# Pump_Agri.net
KiCad netlist of a schematic drawn in Altium Designer
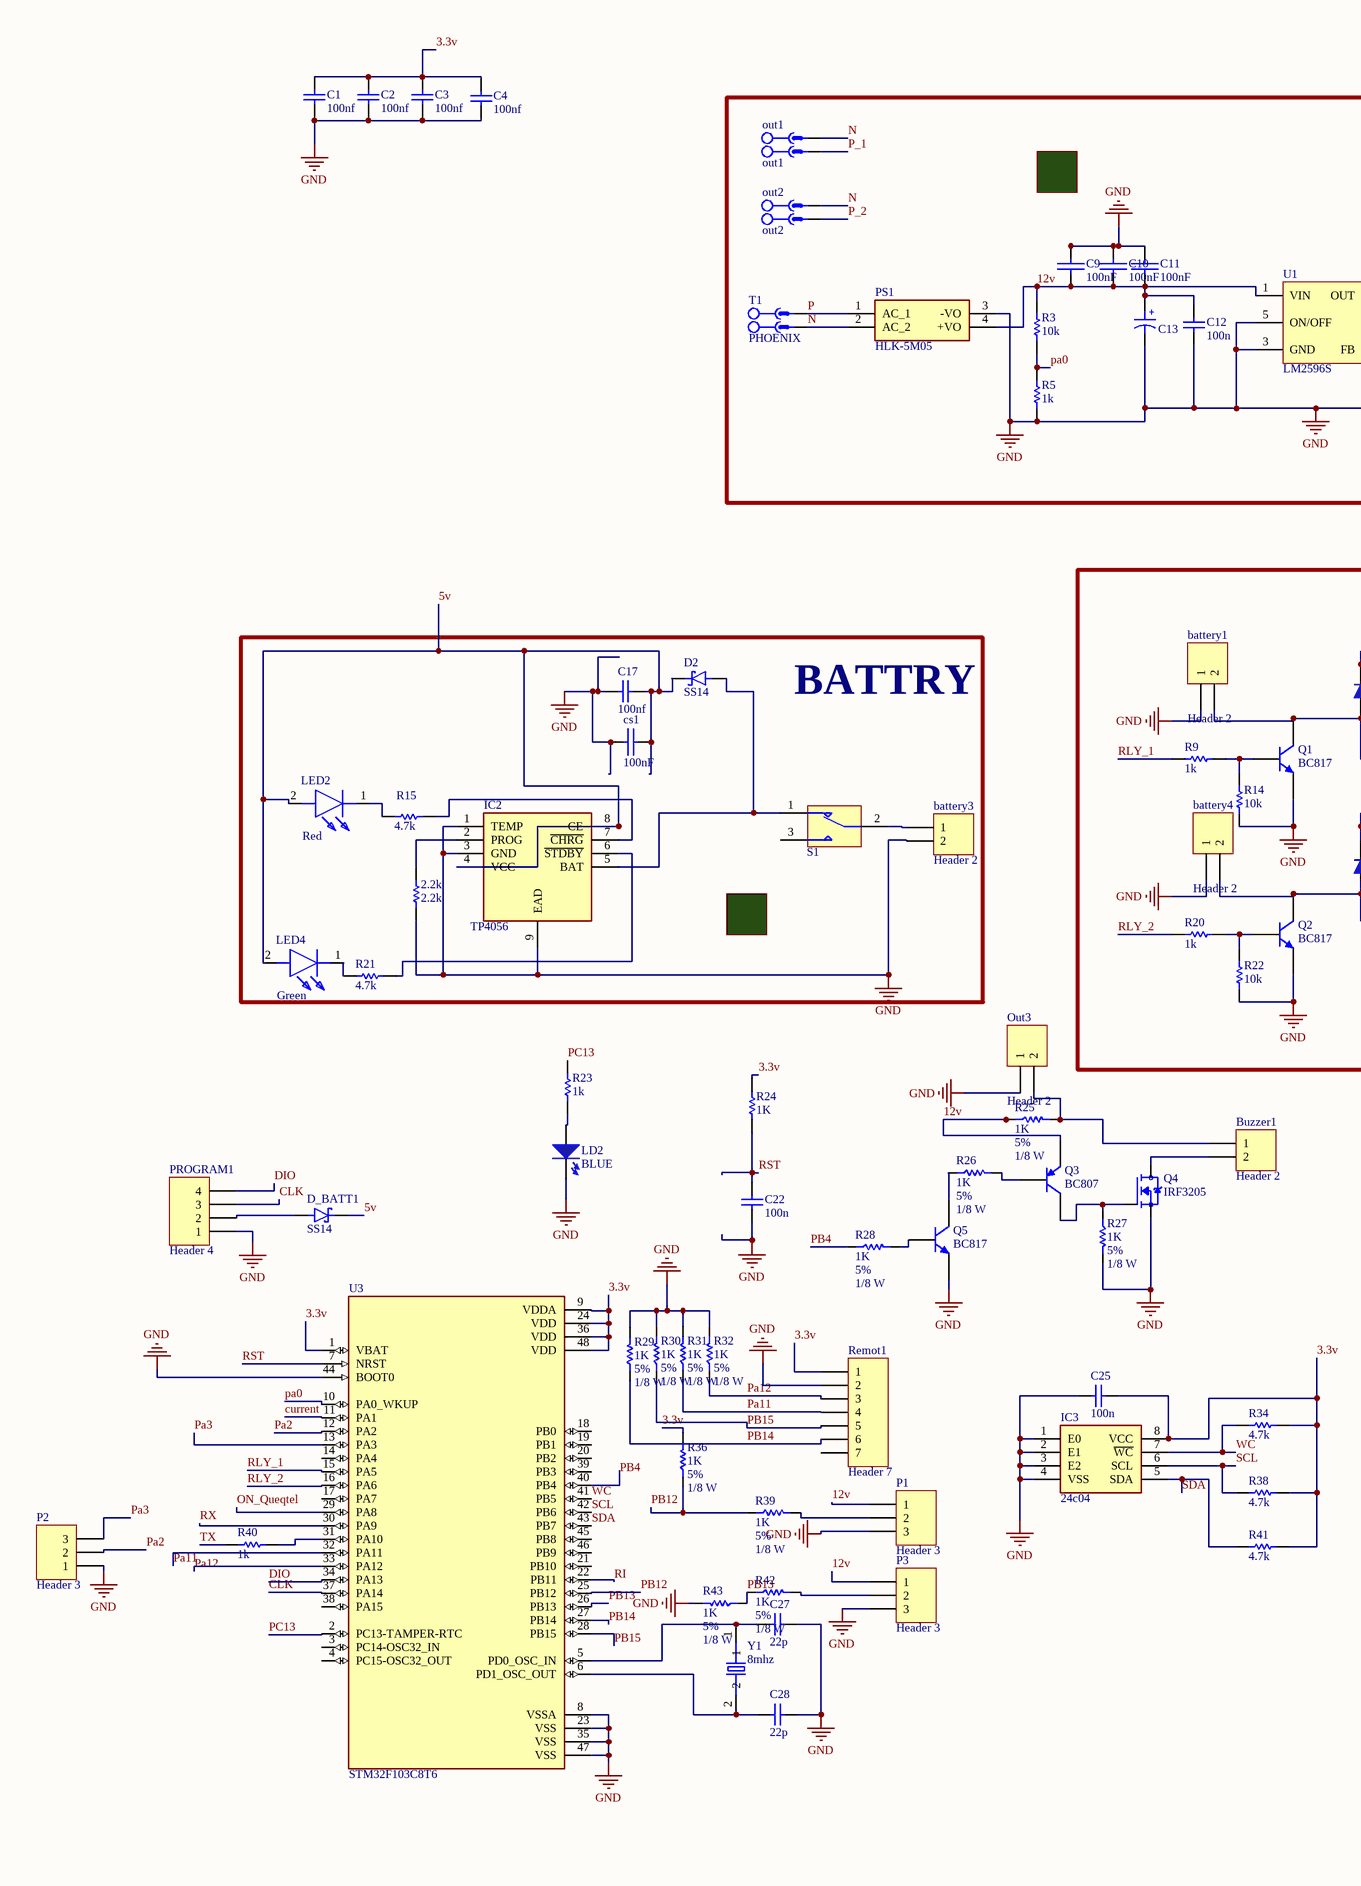
[diagram p0: Pump_Agri.SchDoc, left]
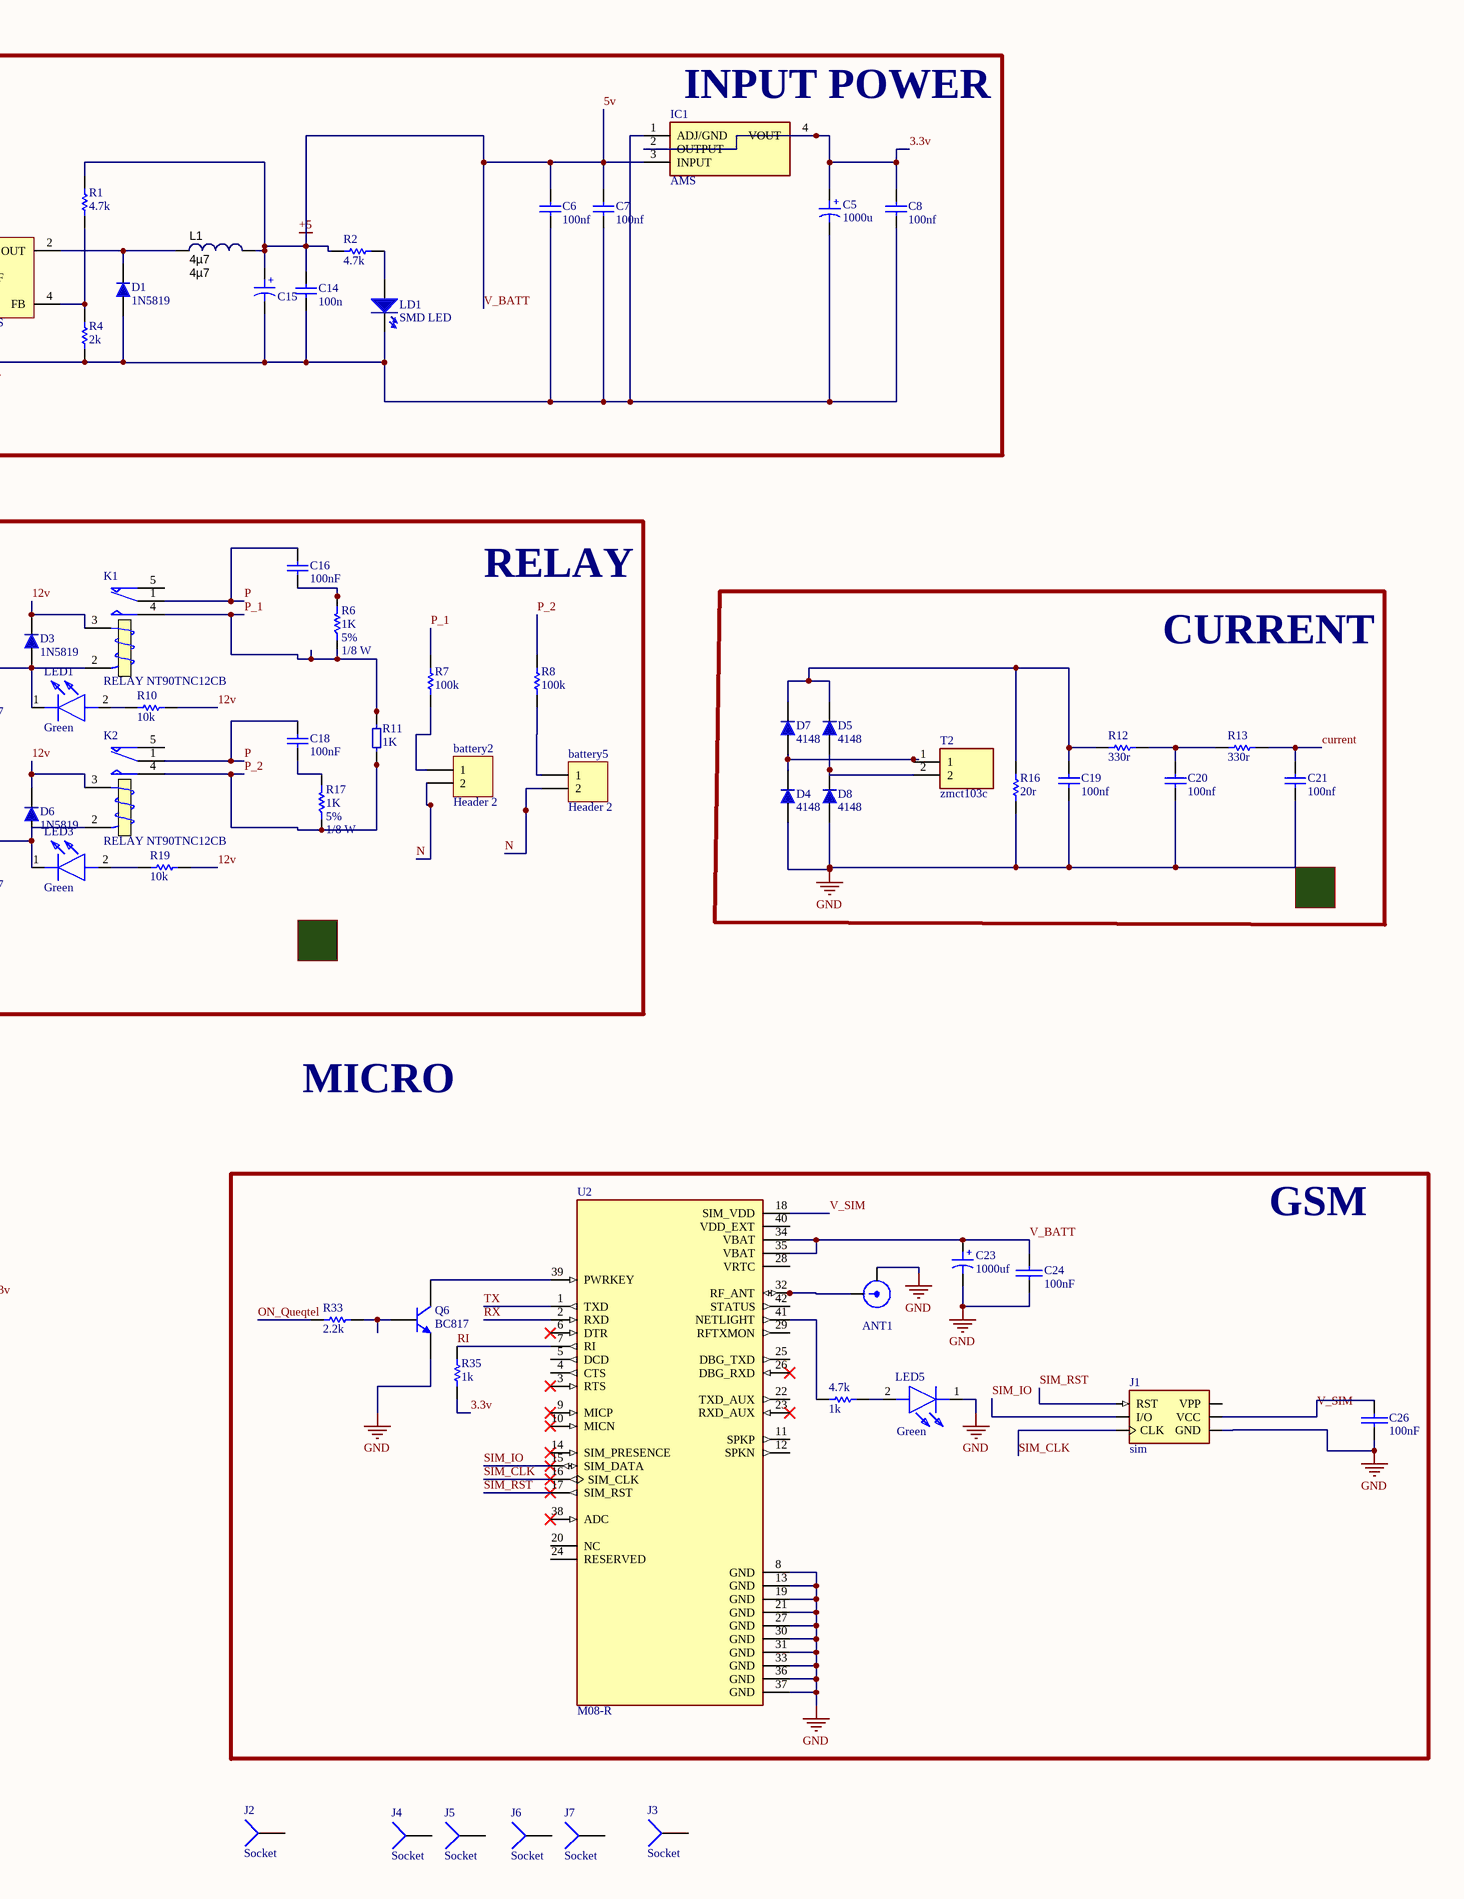
[diagram p1: Pump_Agri.SchDoc, right]

(export (version "E")
  (design (tool "Eeschema 10.0.6"))
  (components
    (comp (ref "2.2k")
      (value "2.2k")
      (footprint "RESC3413X04N")
      (description "RES 0805")
      (fields (field (name "DESIGNER") "Abbas Basereh"))
      (libsource (lib "2017AbbasBasereh9365731239 -ver1") (part "RES 0805 0.125W"))
    )
    (comp (ref "4.7k")
      (value "1k")
      (footprint "RESC3413X04N")
      (description "RES 0805")
      (fields (field (name "DESIGNER") "Abbas Basereh"))
      (libsource (lib "2017AbbasBasereh9365731239 -ver1") (part "RES 0805 0.125W"))
    )
    (comp (ref "ANT1")
      (value "ANT U.FL")
      (footprint "U.FL SMD")
      (description "Antenna")
      (libsource (lib "Altium") (part "ANT U.FL"))
    )
    (comp (ref "battery1")
      (value "Header 2")
      (footprint "HDR1X2")
      (description "Header, 2-Pin")
      (fields (field (name "PUBLISHER") "Altium Limited"))
      (libsource (lib "") (part "Header 2_1"))
    )
    (comp (ref "battery2")
      (value "Header 2")
      (footprint "HDR1X2")
      (description "Header, 2-Pin")
      (fields (field (name "PUBLISHER") "Altium Limited"))
      (libsource (lib "Miscellaneous Connectors") (part "Header 2"))
    )
    (comp (ref "battery3")
      (value "Header 2")
      (footprint "HDR1X2")
      (description "Header, 2-Pin")
      (fields (field (name "PUBLISHER") "Altium Limited"))
      (libsource (lib "Miscellaneous Connectors") (part "Header 2"))
    )
    (comp (ref "battery4")
      (value "Header 2")
      (footprint "HDR1X2")
      (description "Header, 2-Pin")
      (fields (field (name "PUBLISHER") "Altium Limited"))
      (libsource (lib "") (part "Header 2_1"))
    )
    (comp (ref "battery5")
      (value "Header 2")
      (footprint "HDR1X2")
      (description "Header, 2-Pin")
      (fields (field (name "PUBLISHER") "Altium Limited"))
      (libsource (lib "Miscellaneous Connectors") (part "Header 2"))
    )
    (comp (ref "Buzzer1")
      (value "Header 2")
      (footprint "HDR1X2")
      (description "Header, 2-Pin")
      (fields (field (name "PUBLISHER") "Altium Limited"))
      (libsource (lib "Miscellaneous Connectors") (part "Header 2"))
    )
    (comp (ref "C1")
      (value "100nf")
      (footprint "CAPC3413X12N")
      (description "CAP 0805")
      (fields (field (name "DESIGNER") "Abbas Basereh"))
      (libsource (lib "2017AbbasBasereh9365731239 -ver1") (part "CAP SMD 0805"))
    )
    (comp (ref "C2")
      (value "100nf")
      (footprint "CAPC3413X12N")
      (description "CAP 0805")
      (fields (field (name "DESIGNER") "Abbas Basereh"))
      (libsource (lib "2017AbbasBasereh9365731239 -ver1") (part "CAP SMD 0805"))
    )
    (comp (ref "C3")
      (value "100nf")
      (footprint "CAPC3413X12N")
      (description "CAP 0805")
      (fields (field (name "DESIGNER") "Abbas Basereh"))
      (libsource (lib "2017AbbasBasereh9365731239 -ver1") (part "CAP SMD 0805"))
    )
    (comp (ref "C4")
      (value "100nf")
      (footprint "CAPC3413X12N")
      (description "CAP 0805")
      (fields (field (name "DESIGNER") "Abbas Basereh"))
      (libsource (lib "2017AbbasBasereh9365731239 -ver1") (part "CAP SMD 0805"))
    )
    (comp (ref "C5")
      (value "1000u")
      (footprint "Cap electrolitic radial 8x12-3.5")
      (description "Cap electrolitic radial")
      (fields (field (name "DESIGNER") "Abbas Basereh"))
      (libsource (lib "Altium") (part "Cap ELECTROLITIC TOTAL SIZE"))
    )
    (comp (ref "C6")
      (value "100nf")
      (footprint "CAPC3413X12N")
      (description "CAP 0805")
      (fields (field (name "DESIGNER") "Abbas Basereh"))
      (libsource (lib "2017AbbasBasereh9365731239 -ver1") (part "CAP SMD 0805"))
    )
    (comp (ref "C7")
      (value "100nf")
      (footprint "CAPC3413X12N")
      (description "CAP 0805")
      (fields (field (name "DESIGNER") "Abbas Basereh"))
      (libsource (lib "2017AbbasBasereh9365731239 -ver1") (part "CAP SMD 0805"))
    )
    (comp (ref "C8")
      (value "100nf")
      (footprint "CAPC3413X12N")
      (description "CAP 0805")
      (fields (field (name "DESIGNER") "Abbas Basereh"))
      (libsource (lib "2017AbbasBasereh9365731239 -ver1") (part "CAP SMD 0805"))
    )
    (comp (ref "C9")
      (value "100nF")
      (footprint "SMD_CAP_1206")
      (description "Bipolar Capacitor")
      (fields (field (name "VOLTAGE") "100V") (field (name "DESIGNER") "Saeid Jorablo"))
      (libsource (lib "My_Library") (part "Cap-Bipolar"))
    )
    (comp (ref "C10")
      (value "100nF")
      (footprint "SMD_CAP_1206")
      (description "Bipolar Capacitor")
      (fields (field (name "VOLTAGE") "100V") (field (name "DESIGNER") "Saeid Jorablo"))
      (libsource (lib "My_Library") (part "Cap-Bipolar"))
    )
    (comp (ref "C11")
      (value "100nF")
      (footprint "SMD_CAP_1206")
      (description "Bipolar Capacitor")
      (fields (field (name "VOLTAGE") "100V") (field (name "DESIGNER") "Saeid Jorablo"))
      (libsource (lib "My_Library") (part "Cap-Bipolar"))
    )
    (comp (ref "C12")
      (value "100n")
      (footprint "CAPC3413X12N")
      (description "CAP 0805")
      (fields (field (name "DESIGNER") "Abbas Basereh"))
      (libsource (lib "Altium") (part "CAP SMD 0805"))
    )
    (comp (ref "C13")
      (value "1000u")
      (footprint "Cap electrolitic radial 10x20-5")
      (description "Cap electrolitic radial")
      (fields (field (name "DESIGNER") "Abbas Basereh"))
      (libsource (lib "Altium") (part "Cap electrolitic radial 10x21"))
    )
    (comp (ref "C14")
      (value "100n")
      (footprint "CAPC3413X12N")
      (description "CAP 0805")
      (fields (field (name "DESIGNER") "Abbas Basereh"))
      (libsource (lib "Altium") (part "CAP SMD 0805"))
    )
    (comp (ref "C15")
      (value "100u")
      (footprint "Cap electrolitic radial 10x20-5")
      (description "Cap electrolitic radial")
      (fields (field (name "DESIGNER") "Abbas Basereh"))
      (libsource (lib "Altium") (part "Cap electrolitic radial 10x21"))
    )
    (comp (ref "C16")
      (value "100nF")
      (footprint "Cap-10nF-630V")
      (description "CAP Ceramic Total")
      (fields (field (name "DESIGNER") "Ali Hafizi"))
      (libsource (lib "Altium") (part "CAP CERAMIC TOTAL SIZE"))
    )
    (comp (ref "C17")
      (value "100nf")
      (footprint "CAPC3413X12N")
      (description "CAP 0805")
      (fields (field (name "DESIGNER") "Abbas Basereh"))
      (libsource (lib "2017AbbasBasereh9365731239 -ver1") (part "CAP SMD 0805"))
    )
    (comp (ref "C18")
      (value "100nF")
      (footprint "Cap-10nF-630V")
      (description "CAP Ceramic Total")
      (fields (field (name "DESIGNER") "Ali Hafizi"))
      (libsource (lib "Altium") (part "CAP CERAMIC TOTAL SIZE"))
    )
    (comp (ref "C19")
      (value "100nf")
      (footprint "CAPC3413X12N")
      (description "CAP 0805")
      (fields (field (name "DESIGNER") "Abbas Basereh"))
      (libsource (lib "2017AbbasBasereh9365731239 -ver1") (part "CAP SMD 0805"))
    )
    (comp (ref "C20")
      (value "100nf")
      (footprint "CAPC3413X12N")
      (description "CAP 0805")
      (fields (field (name "DESIGNER") "Abbas Basereh"))
      (libsource (lib "2017AbbasBasereh9365731239 -ver1") (part "CAP SMD 0805"))
    )
    (comp (ref "C21")
      (value "100nf")
      (footprint "CAPC3413X12N")
      (description "CAP 0805")
      (fields (field (name "DESIGNER") "Abbas Basereh"))
      (libsource (lib "2017AbbasBasereh9365731239 -ver1") (part "CAP SMD 0805"))
    )
    (comp (ref "C22")
      (value "100n")
      (footprint "CAPC3413X12N")
      (description "CAP 0805")
      (fields (field (name "DESIGNER") "Abbas Basereh"))
      (libsource (lib "Altium") (part "CAP SMD 0805"))
    )
    (comp (ref "C23")
      (value "1000uf")
      (footprint "Cap electrolitic radial 8x12-3.5")
      (description "Cap electrolitic radial")
      (fields (field (name "DESIGNER") "Abbas Basereh"))
      (libsource (lib "Altium") (part "Cap ELECTROLITIC TOTAL SIZE"))
    )
    (comp (ref "C24")
      (value "100nF")
      (footprint "CAP0805")
      (description "Bipolar Capacitor")
      (fields
        (field (name "VOLTAGE") "100V")
        (field (name "Comment") "100N")
        (field (name "DESIGNER") "Saeid Jorablo")
      )
      (libsource (lib "My_Library") (part "Cap-Bipolar"))
    )
    (comp (ref "C25")
      (value "100n")
      (footprint "CAPC3413X12N")
      (description "CAP 0805")
      (fields (field (name "DESIGNER") "Abbas Basereh"))
      (libsource (lib "Altium") (part "CAP SMD 0805"))
    )
    (comp (ref "C26")
      (value "100nF")
      (footprint "CAP0805")
      (description "Bipolar Capacitor")
      (fields
        (field (name "VOLTAGE") "100V")
        (field (name "Comment") "100N")
        (field (name "DESIGNER") "Saeid Jorablo")
      )
      (libsource (lib "My_Library") (part "Cap-Bipolar"))
    )
    (comp (ref "C27")
      (value "22p")
      (footprint "CAPC3413X12N")
      (description "CAP 0805")
      (fields (field (name "DESIGNER") "Abbas Basereh"))
      (libsource (lib "2017AbbasBasereh9365731239 -ver1") (part "CAP SMD 0805"))
    )
    (comp (ref "C28")
      (value "22p")
      (footprint "CAPC3413X12N")
      (description "CAP 0805")
      (fields (field (name "DESIGNER") "Abbas Basereh"))
      (libsource (lib "2017AbbasBasereh9365731239 -ver1") (part "CAP SMD 0805"))
    )
    (comp (ref "cs1")
      (value "100nF")
      (footprint "SMD_CAP_1206")
      (description "Bipolar Capacitor")
      (fields (field (name "VOLTAGE") "100V") (field (name "DESIGNER") "Saeid Jorablo"))
      (libsource (lib "My_Library") (part "Cap-Bipolar"))
    )
    (comp (ref "D1")
      (value "1N5819")
      (footprint "DO-214AA(SMA)")
      (libsource (lib "ZetaBoard Altium Lib 14000319") (part "1N5819(SS14)"))
    )
    (comp (ref "D2")
      (value "SS14")
      (footprint "DIOM4325X250N")
      (description "1A, 40V, Schottky Rectifier")
      (fields (field (name "MF") "Taiwan Semiconductor"))
      (libsource (lib "SS14") (part "SS14"))
    )
    (comp (ref "D3")
      (value "1N5819")
      (footprint "DO-214AA(SMA)")
      (libsource (lib "ZetaBoard Altium Lib 14000319") (part "1N5819(SS14)"))
    )
    (comp (ref "D4")
      (value "4148")
      (footprint "SOD80, LL-34")
      (description "DIODE GEN PURP 75V 200MA DO213AA")
      (fields (field (name "PUBLISHER") "Abbas Basereh"))
      (libsource (lib "2017AbbasBasereh9365731239 -ver1") (part "1N4148UR-1"))
    )
    (comp (ref "D5")
      (value "4148")
      (footprint "SOD80, LL-34")
      (description "DIODE GEN PURP 75V 200MA DO213AA")
      (fields (field (name "PUBLISHER") "Abbas Basereh"))
      (libsource (lib "2017AbbasBasereh9365731239 -ver1") (part "1N4148UR-1"))
    )
    (comp (ref "D6")
      (value "1N5819")
      (footprint "DO-214AA(SMA)")
      (libsource (lib "ZetaBoard Altium Lib 14000319") (part "1N5819(SS14)"))
    )
    (comp (ref "D7")
      (value "4148")
      (footprint "SOD80, LL-34")
      (description "DIODE GEN PURP 75V 200MA DO213AA")
      (fields (field (name "PUBLISHER") "Abbas Basereh"))
      (libsource (lib "2017AbbasBasereh9365731239 -ver1") (part "1N4148UR-1"))
    )
    (comp (ref "D8")
      (value "4148")
      (footprint "SOD80, LL-34")
      (description "DIODE GEN PURP 75V 200MA DO213AA")
      (fields (field (name "PUBLISHER") "Abbas Basereh"))
      (libsource (lib "2017AbbasBasereh9365731239 -ver1") (part "1N4148UR-1"))
    )
    (comp (ref "D_BATT1") (value "SS14") (footprint "DIOM4325X250N") (libsource (lib "SS14") (part "SS14")))
    (comp (ref "IC1")
      (value "AMS")
      (footprint "SamacSys:SOT230P700X180-4N")
      (description "Integrated Circuit")
      (fields
        (field (name "MANUFACTURER_PART_NUMBER") "LM1117IMPX-ADJ/NOPB")
        (field (name "MOUSER PART NUMBER") "926-M1117IMPXADJNOPB")
      )
      (libsource (lib "*") (part "LM1117IMPX-ADJ_NOPB"))
    )
    (comp (ref "IC2")
      (value "TP4056")
      (footprint "SamacSys:SOIC127P600X175-9N")
      (description "Integrated Circuit")
      (fields (field (name "MANUFACTURER_PART_NUMBER") "TP4056X"))
      (libsource (lib "*") (part "TP4056X"))
    )
    (comp (ref "IC3")
      (value "24c04")
      (footprint "SamacSys:SOIC127P600X175-8N")
      (description "Integrated Circuit")
      (fields
        (field (name "MANUFACTURER_PART_NUMBER") "M24C02-RMN6P")
        (field (name "MOUSER PART NUMBER") "511-M24C02-RMN6P")
      )
      (libsource (lib "*") (part "M24C02-RMN6P"))
    )
    (comp (ref "J1")
      (value "sim")
      (footprint "GCT_SIM5060-6-0-26-01-X_REVC")
      (description "SIM Card Connector, Hinged Type 6 Pin, SMT, 2.6mm Profile, Optional Locating Post")
      (fields (field (name "MP") "SIM5060-6-0-26-01-X") (field (name "MF") "Global Connector Technology"))
      (libsource (lib "SIM5060-6-0-26-01-X_REVC") (part "SIM5060-6-0-26-01-X_REVC"))
    )
    (comp (ref "J2")
      (value "Socket")
      (footprint "Test Point")
      (fields (field (name "PUBLISHER") "Altium Limited"))
      (libsource (lib "Miscellaneous Connectors") (part "Socket"))
    )
    (comp (ref "J3")
      (value "Socket")
      (footprint "Test Point")
      (fields (field (name "PUBLISHER") "Altium Limited"))
      (libsource (lib "Miscellaneous Connectors") (part "Socket"))
    )
    (comp (ref "J4")
      (value "Socket")
      (footprint "Test Point")
      (fields (field (name "PUBLISHER") "Altium Limited"))
      (libsource (lib "Miscellaneous Connectors") (part "Socket"))
    )
    (comp (ref "J5")
      (value "Socket")
      (footprint "Test Point")
      (fields (field (name "PUBLISHER") "Altium Limited"))
      (libsource (lib "Miscellaneous Connectors") (part "Socket"))
    )
    (comp (ref "J6")
      (value "Socket")
      (footprint "Test Point")
      (fields (field (name "PUBLISHER") "Altium Limited"))
      (libsource (lib "Miscellaneous Connectors") (part "Socket"))
    )
    (comp (ref "J7")
      (value "Socket")
      (footprint "Test Point")
      (fields (field (name "PUBLISHER") "Altium Limited"))
      (libsource (lib "Miscellaneous Connectors") (part "Socket"))
    )
    (comp (ref "K1")
      (value "RELAY NT90TNC12CB")
      (footprint "RELAY NT90TNC12CB")
      (description "Relay_SPDT POWER NEEDLE")
      (fields (field (name "DESIGNER") "Abbas Basereh"))
      (libsource (lib "2017AbbasBasereh9365731239 -ver1") (part "RELAY NT90TNC12CB"))
    )
    (comp (ref "K2")
      (value "RELAY NT90TNC12CB")
      (footprint "RELAY NT90TNC12CB")
      (description "Relay_SPDT POWER NEEDLE")
      (fields (field (name "DESIGNER") "Abbas Basereh"))
      (libsource (lib "2017AbbasBasereh9365731239 -ver1") (part "RELAY NT90TNC12CB"))
    )
    (comp (ref "L1")
      (value "4µ7")
      (footprint "Inductor SMD 3x3.2mm")
      (description "Inductor 4.7µH SMD 3x3.2mm")
      (fields (field (name "TOLERANCE") "±20%") (field (name "ALTIUM_VALUE") "4µ7"))
      (libsource (lib "2017AbbasBasereh9365731239 -ver1") (part "Inductor 4.7µH SMD 3x3.2mm"))
    )
    (comp (ref "LD1")
      (value "SMD LED")
      (footprint "LED_0805 G")
      (libsource (lib "ZetaBoard Altium Lib 14000319") (part "LED SMD"))
    )
    (comp (ref "LD2")
      (value "BLUE")
      (footprint "LED_0805 G")
      (libsource (lib "ZetaBoard Altium Lib 14000319") (part "LED SMD"))
    )
    (comp (ref "LED1")
      (value "Green")
      (footprint "SamacSys:LEDC2012X80N")
      (description "LED")
      (fields
        (field (name "MANUFACTURER_PART_NUMBER") "150080BS75000")
        (field (name "MOUSER PART NUMBER") "710-150080BS75000")
      )
      (libsource (lib "*") (part "150080BS75000"))
    )
    (comp (ref "LED2")
      (value "Red")
      (footprint "SamacSys:LEDC2012X80N")
      (description "LED")
      (fields
        (field (name "MANUFACTURER_PART_NUMBER") "150080BS75000")
        (field (name "MOUSER PART NUMBER") "710-150080BS75000")
      )
      (libsource (lib "*") (part "150080BS75000"))
    )
    (comp (ref "LED3")
      (value "Green")
      (footprint "SamacSys:LEDC2012X80N")
      (description "LED")
      (fields
        (field (name "MANUFACTURER_PART_NUMBER") "150080BS75000")
        (field (name "MOUSER PART NUMBER") "710-150080BS75000")
      )
      (libsource (lib "*") (part "150080BS75000"))
    )
    (comp (ref "LED4")
      (value "Green")
      (footprint "SamacSys:LEDC2012X80N")
      (description "LED")
      (fields
        (field (name "MANUFACTURER_PART_NUMBER") "150080BS75000")
        (field (name "MOUSER PART NUMBER") "710-150080BS75000")
      )
      (libsource (lib "*") (part "150080BS75000"))
    )
    (comp (ref "LED5")
      (value "Green")
      (footprint "SamacSys:LEDC2012X80N")
      (description "LED")
      (fields
        (field (name "MANUFACTURER_PART_NUMBER") "150080BS75000")
        (field (name "MOUSER PART NUMBER") "710-150080BS75000")
      )
      (libsource (lib "*") (part "150080BS75000"))
    )
    (comp (ref "out1")
      (value "out1")
      (footprint "MSTBV 2,5/2-G-5")
      (description "2 Pitch: 5 mm Color: green Contact surface: Tin Assembly")
      (fields
        (field (name "MANUFACTURER") "PHOENIX CONTACT")
        (field (name "VOLTAGE") "320 V")
        (field (name "DESIGNER") "ABBAS BASEREH")
      )
      (libsource (lib "Altium") (part "CON_Phoenix_MSTBV_02"))
    )
    (comp (ref "out2")
      (value "out2")
      (footprint "MSTBV 2,5/2-G-5")
      (description "2 Pitch: 5 mm Color: green Contact surface: Tin Assembly")
      (fields
        (field (name "MANUFACTURER") "PHOENIX CONTACT")
        (field (name "VOLTAGE") "320 V")
        (field (name "DESIGNER") "ABBAS BASEREH")
      )
      (libsource (lib "Altium") (part "CON_Phoenix_MSTBV_02"))
    )
    (comp (ref "Out3")
      (value "Header 2")
      (footprint "HDR1X2")
      (description "Header, 2-Pin")
      (fields (field (name "PUBLISHER") "Altium Limited"))
      (libsource (lib "") (part "Header 2_1"))
    )
    (comp (ref "P1")
      (value "Header 3")
      (footprint "HDR1X3")
      (description "Header, 3-Pin")
      (fields (field (name "PUBLISHER") "Altium Limited"))
      (libsource (lib "Altium") (part "Header 3"))
    )
    (comp (ref "P2")
      (value "Header 3")
      (footprint "HDR1X3")
      (description "Header, 3-Pin")
      (fields (field (name "PUBLISHER") "Altium Limited"))
      (libsource (lib "") (part "Header 3_1"))
    )
    (comp (ref "P3")
      (value "Header 3")
      (footprint "HDR1X3")
      (description "Header, 3-Pin")
      (fields (field (name "PUBLISHER") "Altium Limited"))
      (libsource (lib "Altium") (part "Header 3"))
    )
    (comp (ref "PROGRAM1")
      (value "Header 4")
      (footprint "HDR1X4")
      (description "Header, 4-Pin")
      (fields (field (name "PUBLISHER") "Altium Limited"))
      (libsource (lib "Miscellaneous Connectors") (part "Header 4"))
    )
    (comp (ref "PS1")
      (value "HLK-5M05")
      (footprint "SamacSys:HLK5M05")
      (description "Power Supply")
      (libsource (lib "*") (part "HLK-5M05"))
    )
    (comp (ref "Q1")
      (value "BC817")
      (footprint "SOT-23")
      (libsource (lib "ZetaBoard Altium Lib 14000319") (part "BC817"))
    )
    (comp (ref "Q2")
      (value "BC817")
      (footprint "SOT-23")
      (libsource (lib "ZetaBoard Altium Lib 14000319") (part "BC817"))
    )
    (comp (ref "Q3")
      (value "BC807")
      (footprint "SOT23_BEC_N")
      (description "PNP Bipolar Transistor")
      (fields (field (name "PUBLISHER") "Altium Limited"))
      (libsource (lib "My_Library") (part "PNP"))
    )
    (comp (ref "Q4")
      (value "IRF3205")
      (footprint "TO254P1041X444X2933-3")
      (description "N-Channel 55V 110A (Tc) 200W (Tc) Through Hole TO-220AB")
      (fields (field (name "MF") "Infineon Technologies"))
      (libsource (lib "IRF3205") (part "IRF3205"))
    )
    (comp (ref "Q5")
      (value "BC817")
      (footprint "SOT23_BEC_N")
      (description "NPN Bipolar Transistor")
      (fields (field (name "PUBLISHER") "Altium Limited"))
      (libsource (lib "My_Library") (part "NPN"))
    )
    (comp (ref "Q6")
      (value "BC817")
      (footprint "SOT-23")
      (libsource (lib "ZetaBoard Altium Lib 14000319") (part "BC817"))
    )
    (comp (ref "R1")
      (value "4.7k")
      (footprint "RESC3413X04N")
      (description "RES 0805")
      (fields (field (name "DESIGNER") "Abbas Basereh"))
      (libsource (lib "2017AbbasBasereh9365731239 -ver1") (part "RES 0805 0.125W"))
    )
    (comp (ref "R2")
      (value "4.7k")
      (footprint "RESC3413X04N")
      (description "RES 0805")
      (fields (field (name "DESIGNER") "Abbas Basereh"))
      (libsource (lib "Altium") (part "RES 0805 0.125W"))
    )
    (comp (ref "R3")
      (value "10k")
      (footprint "RESC3413X04N")
      (description "RES 0805")
      (fields (field (name "DESIGNER") "Abbas Basereh"))
      (libsource (lib "2017AbbasBasereh9365731239 -ver1") (part "RES 0805 0.125W"))
    )
    (comp (ref "R4")
      (value "2k")
      (footprint "RESC3413X04N")
      (description "RES 0805")
      (fields (field (name "DESIGNER") "Abbas Basereh"))
      (libsource (lib "2017AbbasBasereh9365731239 -ver1") (part "RES 0805 0.125W"))
    )
    (comp (ref "R5")
      (value "1k")
      (footprint "RESC3413X04N")
      (description "RES 0805")
      (fields (field (name "DESIGNER") "Abbas Basereh"))
      (libsource (lib "2017AbbasBasereh9365731239 -ver1") (part "RES 0805 0.125W"))
    )
    (comp (ref "R6")
      (value "1K")
      (footprint "Res-(1/4)-Stand")
      (description "Resistor")
      (fields (field (name "TOLERANCE") "5%") (field (name "POWER") "1/8 W"))
      (libsource (lib "My_Library") (part "Resistor"))
    )
    (comp (ref "R7")
      (value "100k")
      (footprint "RESC3413X04N")
      (description "RES 0805")
      (fields (field (name "DESIGNER") "Abbas Basereh"))
      (libsource (lib "2017AbbasBasereh9365731239 -ver1") (part "RES 0805 0.125W"))
    )
    (comp (ref "R8")
      (value "100k")
      (footprint "RESC3413X04N")
      (description "RES 0805")
      (fields (field (name "DESIGNER") "Abbas Basereh"))
      (libsource (lib "2017AbbasBasereh9365731239 -ver1") (part "RES 0805 0.125W"))
    )
    (comp (ref "R9")
      (value "1k")
      (footprint "RESC3413X04N")
      (description "RES 0805")
      (fields (field (name "DESIGNER") "Abbas Basereh"))
      (libsource (lib "2017AbbasBasereh9365731239 -ver1") (part "RES 0805 0.125W"))
    )
    (comp (ref "R10")
      (value "10k")
      (footprint "RESC3413X04N")
      (description "RES 0805")
      (fields (field (name "DESIGNER") "Abbas Basereh"))
      (libsource (lib "2017AbbasBasereh9365731239 -ver1") (part "RES 0805 0.125W"))
    )
    (comp (ref "R11")
      (value "Resistor SMD")
      (footprint "2512 Resistor")
      (fields (field (name "ALTIUM_UNNAMED_1") "1K"))
      (libsource (lib "ZetaBoard Altium Lib 14000319") (part "Resistor SMD"))
    )
    (comp (ref "R12")
      (value "330r")
      (footprint "RESC3413X04N")
      (description "RES 0805")
      (fields (field (name "DESIGNER") "Abbas Basereh"))
      (libsource (lib "2017AbbasBasereh9365731239 -ver1") (part "RES 0805 0.125W"))
    )
    (comp (ref "R13")
      (value "330r")
      (footprint "RESC3413X04N")
      (description "RES 0805")
      (fields (field (name "DESIGNER") "Abbas Basereh"))
      (libsource (lib "2017AbbasBasereh9365731239 -ver1") (part "RES 0805 0.125W"))
    )
    (comp (ref "R14")
      (value "10k")
      (footprint "RESC3413X04N")
      (description "RES 0805")
      (fields (field (name "DESIGNER") "Abbas Basereh"))
      (libsource (lib "2017AbbasBasereh9365731239 -ver1") (part "RES 0805 0.125W"))
    )
    (comp (ref "R15")
      (value "4.7k")
      (footprint "RESC3413X04N")
      (description "RES 0805")
      (fields (field (name "DESIGNER") "Abbas Basereh"))
      (libsource (lib "2017AbbasBasereh9365731239 -ver1") (part "RES 0805 0.125W"))
    )
    (comp (ref "R16")
      (value "20r")
      (footprint "RESC3413X04N")
      (description "RES 0805")
      (fields (field (name "DESIGNER") "Abbas Basereh"))
      (libsource (lib "2017AbbasBasereh9365731239 -ver1") (part "RES 0805 0.125W"))
    )
    (comp (ref "R17")
      (value "1K")
      (footprint "Res-(1/4)-Stand")
      (description "Resistor")
      (fields (field (name "TOLERANCE") "5%") (field (name "POWER") "1/8 W"))
      (libsource (lib "My_Library") (part "Resistor"))
    )
    (comp (ref "R19")
      (value "10k")
      (footprint "RESC3413X04N")
      (description "RES 0805")
      (fields (field (name "DESIGNER") "Abbas Basereh"))
      (libsource (lib "2017AbbasBasereh9365731239 -ver1") (part "RES 0805 0.125W"))
    )
    (comp (ref "R20")
      (value "1k")
      (footprint "RESC3413X04N")
      (description "RES 0805")
      (fields (field (name "DESIGNER") "Abbas Basereh"))
      (libsource (lib "2017AbbasBasereh9365731239 -ver1") (part "RES 0805 0.125W"))
    )
    (comp (ref "R21")
      (value "4.7k")
      (footprint "RESC3413X04N")
      (description "RES 0805")
      (fields (field (name "DESIGNER") "Abbas Basereh"))
      (libsource (lib "2017AbbasBasereh9365731239 -ver1") (part "RES 0805 0.125W"))
    )
    (comp (ref "R22")
      (value "10k")
      (footprint "RESC3413X04N")
      (description "RES 0805")
      (fields (field (name "DESIGNER") "Abbas Basereh"))
      (libsource (lib "2017AbbasBasereh9365731239 -ver1") (part "RES 0805 0.125W"))
    )
    (comp (ref "R23")
      (value "1k")
      (footprint "RESC3413X04N")
      (description "RES 0805")
      (fields (field (name "DESIGNER") "Abbas Basereh"))
      (libsource (lib "Altium") (part "RES 0805 0.125W"))
    )
    (comp (ref "R24")
      (value "1K")
      (footprint "RESC3413X04N")
      (description "RES 0805")
      (fields (field (name "DESIGNER") "Abbas Basereh"))
      (libsource (lib "Altium") (part "RES 0805 0.125W"))
    )
    (comp (ref "R25")
      (value "1K")
      (footprint "RES 1206 (3216X08L)")
      (description "Resistor")
      (fields (field (name "TOLERANCE") "5%") (field (name "POWER") "1/8 W"))
      (libsource (lib "My_Library") (part "Resistor"))
    )
    (comp (ref "R26")
      (value "1K")
      (footprint "RES 1206 (3216X08L)")
      (description "Resistor")
      (fields (field (name "TOLERANCE") "5%") (field (name "POWER") "1/8 W") (field (name "Comment") "4.7k"))
      (libsource (lib "My_Library") (part "Resistor"))
    )
    (comp (ref "R27")
      (value "1K")
      (footprint "RES 1206 (3216X08L)")
      (description "Resistor")
      (fields (field (name "TOLERANCE") "5%") (field (name "POWER") "1/8 W") (field (name "Comment") "10k"))
      (libsource (lib "My_Library") (part "Resistor"))
    )
    (comp (ref "R28")
      (value "1K")
      (footprint "RES 1206 (3216X08L)")
      (description "Resistor")
      (fields (field (name "TOLERANCE") "5%") (field (name "POWER") "1/8 W") (field (name "Comment") "4.7k"))
      (libsource (lib "My_Library") (part "Resistor"))
    )
    (comp (ref "R29")
      (value "1K")
      (footprint "SMD_RES_1206")
      (description "Resistor")
      (fields (field (name "TOLERANCE") "5%") (field (name "POWER") "1/8 W"))
      (libsource (lib "My_Library") (part "Resistor"))
    )
    (comp (ref "R30")
      (value "1K")
      (footprint "SMD_RES_1206")
      (description "Resistor")
      (fields (field (name "TOLERANCE") "5%") (field (name "POWER") "1/8 W"))
      (libsource (lib "My_Library") (part "Resistor"))
    )
    (comp (ref "R31")
      (value "1K")
      (footprint "SMD_RES_1206")
      (description "Resistor")
      (fields (field (name "TOLERANCE") "5%") (field (name "POWER") "1/8 W"))
      (libsource (lib "My_Library") (part "Resistor"))
    )
    (comp (ref "R32")
      (value "1K")
      (footprint "SMD_RES_1206")
      (description "Resistor")
      (fields (field (name "TOLERANCE") "5%") (field (name "POWER") "1/8 W"))
      (libsource (lib "My_Library") (part "Resistor"))
    )
    (comp (ref "R33")
      (value "2.2k")
      (footprint "RESC3413X04N")
      (description "RES 0805")
      (fields (field (name "DESIGNER") "Abbas Basereh"))
      (libsource (lib "2017AbbasBasereh9365731239 -ver1") (part "RES 0805 0.125W"))
    )
    (comp (ref "R34")
      (value "4.7k")
      (footprint "RESC3413X04N")
      (description "RES 0805")
      (fields (field (name "DESIGNER") "Abbas Basereh"))
      (libsource (lib "2017AbbasBasereh9365731239 -ver1") (part "RES 0805 0.125W"))
    )
    (comp (ref "R35")
      (value "1k")
      (footprint "RESC3413X04N")
      (description "RES 0805")
      (fields (field (name "DESIGNER") "Abbas Basereh"))
      (libsource (lib "2017AbbasBasereh9365731239 -ver1") (part "RES 0805 0.125W"))
    )
    (comp (ref "R36")
      (value "1K")
      (footprint "SMD_RES_1206")
      (description "Resistor")
      (fields (field (name "TOLERANCE") "5%") (field (name "POWER") "1/8 W") (field (name "Comment") "4.7k"))
      (libsource (lib "My_Library") (part "Resistor"))
    )
    (comp (ref "R38")
      (value "4.7k")
      (footprint "RESC3413X04N")
      (description "RES 0805")
      (fields (field (name "DESIGNER") "Abbas Basereh"))
      (libsource (lib "2017AbbasBasereh9365731239 -ver1") (part "RES 0805 0.125W"))
    )
    (comp (ref "R39")
      (value "1K")
      (footprint "SMD_RES_1206")
      (description "Resistor")
      (fields (field (name "TOLERANCE") "5%") (field (name "POWER") "1/8 W") (field (name "Comment") "330r"))
      (libsource (lib "My_Library") (part "Resistor"))
    )
    (comp (ref "R40")
      (value "1k")
      (footprint "RESC3413X04N")
      (description "RES 0805")
      (fields (field (name "DESIGNER") "Abbas Basereh"))
      (libsource (lib "2017AbbasBasereh9365731239 -ver1") (part "RES 0805 0.125W"))
    )
    (comp (ref "R41")
      (value "4.7k")
      (footprint "RESC3413X04N")
      (description "RES 0805")
      (fields (field (name "DESIGNER") "Abbas Basereh"))
      (libsource (lib "2017AbbasBasereh9365731239 -ver1") (part "RES 0805 0.125W"))
    )
    (comp (ref "R42")
      (value "1K")
      (footprint "SMD_RES_1206")
      (description "Resistor")
      (fields (field (name "TOLERANCE") "5%") (field (name "POWER") "1/8 W") (field (name "Comment") "10k"))
      (libsource (lib "My_Library") (part "Resistor"))
    )
    (comp (ref "R43")
      (value "1K")
      (footprint "SMD_RES_1206")
      (description "Resistor")
      (fields (field (name "TOLERANCE") "5%") (field (name "POWER") "1/8 W") (field (name "Comment") "2.2k"))
      (libsource (lib "My_Library") (part "Resistor"))
    )
    (comp (ref "Remot1")
      (value "Header 7")
      (footprint "HDR1X7")
      (description "Header, 7-Pin")
      (fields (field (name "PUBLISHER") "Altium Limited"))
      (libsource (lib "Miscellaneous Connectors") (part "Header 7"))
    )
    (comp (ref "S1")
      (value "Switch SPDT_Subminiator")
      (footprint "SPDT Subminiator")
      (description "Subminiator SPDT Switch")
      (libsource (lib "Altium") (part "Switch SPDT_Subminiator"))
    )
    (comp (ref "T1")
      (value "PHOENIX")
      (footprint "MSTBV 2,5/2-G-5")
      (description "2 Pitch: 5 mm Color: green Contact surface: Tin Assembly")
      (fields
        (field (name "MANUFACTURER") "PHOENIX CONTACT")
        (field (name "VOLTAGE") "320 V")
        (field (name "DESIGNER") "ABBAS BASEREH")
      )
      (libsource (lib "Altium") (part "CON_Phoenix_MSTBV_02"))
    )
    (comp (ref "T2")
      (value "zmct103c")
      (footprint "SamacSys:zmct103c")
      (description "Transformer")
      (libsource (lib "*") (part "zmct103c"))
    )
    (comp (ref "U1")
      (value "LM2596S")
      (footprint "TO - 263")
      (libsource (lib "ZetaBoard Altium Lib 14000319") (part "LM2596S"))
    )
    (comp (ref "U2") (value "M08-R") (footprint "XCVR_M08-R") (libsource (lib "M08-R") (part "M08-R")))
    (comp (ref "U3")
      (value "STM32F103C8T6")
      (footprint "QFP50P900X900X160-48N")
      (description "ARM® Cortex®-M3 STM32F1 Microcontroller IC 32-Bit 72MHz 64KB (64K x 8) FLASH 48-LQFP (7x7)")
      (fields (field (name "MF") "STMicroelectronics"))
      (libsource (lib "STM32F103C8T6") (part "STM32F103C8T6"))
    )
    (comp (ref "Y1")
      (value "8mhz")
      (footprint "XTAL1170X500X450")
      (fields (field (name "MF") "Fox Electronics") (field (name "MP") "FOXSDLF/120-20"))
      (libsource (lib "FOXSDLF_120-20") (part "FOXSDLF/120-20"))
    )
  )
  (nets
    (net (code "1") (name "+5") (class "Default")
      (node (ref "C14") (pin "2") (pinfunction "2_2") (pintype "passive"))
      (node (ref "C15") (pin "1") (pinfunction "1_1") (pintype "passive"))
      (node (ref "C17") (pin "1") (pinfunction "1_1") (pintype "passive"))
      (node (ref "C23") (pin "1") (pinfunction "1_1") (pintype "passive"))
      (node (ref "C24") (pin "1") (pinfunction "+_1") (pintype "passive"))
      (node (ref "C6") (pin "1") (pinfunction "1_1") (pintype "passive"))
      (node (ref "C7") (pin "1") (pinfunction "1_1") (pintype "passive"))
      (node (ref "D2") (pin "C") (pinfunction "K_C") (pintype "passive"))
      (node (ref "D_BATT1") (pin "C") (pinfunction "K_C") (pintype "passive"))
      (node (ref "IC1") (pin "3") (pinfunction "INPUT_3") (pintype "passive"))
      (node (ref "IC2") (pin "4") (pinfunction "VCC_4") (pintype "passive"))
      (node (ref "IC2") (pin "8") (pinfunction "CE_8") (pintype "passive"))
      (node (ref "L1") (pin "2") (pinfunction "2_2") (pintype "passive"))
      (node (ref "LED2") (pin "2") (pinfunction "A_2") (pintype "passive"))
      (node (ref "LED4") (pin "2") (pinfunction "A_2") (pintype "passive"))
      (node (ref "R1") (pin "2") (pinfunction "2_2") (pintype "passive"))
      (node (ref "R2") (pin "1") (pinfunction "1_1") (pintype "passive"))
      (node (ref "U2") (pin "34") (pinfunction "VBAT_34") (pintype "power_in"))
      (node (ref "U2") (pin "35") (pinfunction "VBAT_35") (pintype "power_in"))
      (node (ref "cs1") (pin "2") (pinfunction "-_2") (pintype "passive"))
    )
    (net (code "2") (name "/3.3v") (class "Default")
      (node (ref "C1") (pin "2") (pinfunction "2_2") (pintype "passive"))
      (node (ref "C2") (pin "2") (pinfunction "2_2") (pintype "passive"))
      (node (ref "C25") (pin "1") (pinfunction "1_1") (pintype "passive"))
      (node (ref "C3") (pin "2") (pinfunction "2_2") (pintype "passive"))
      (node (ref "C4") (pin "2") (pinfunction "2_2") (pintype "passive"))
      (node (ref "C5") (pin "1") (pinfunction "1_1") (pintype "passive"))
      (node (ref "C8") (pin "1") (pinfunction "1_1") (pintype "passive"))
      (node (ref "IC1") (pin "2") (pinfunction "OUTPUT_2") (pintype "passive"))
      (node (ref "IC1") (pin "4") (pinfunction "VOUT_4") (pintype "passive"))
      (node (ref "IC3") (pin "8") (pinfunction "VCC_8") (pintype "passive"))
      (node (ref "R24") (pin "2") (pinfunction "2_2") (pintype "passive"))
      (node (ref "R34") (pin "2") (pinfunction "2_2") (pintype "passive"))
      (node (ref "R35") (pin "2") (pinfunction "2_2") (pintype "passive"))
      (node (ref "R36") (pin "2") (pinfunction "2_2") (pintype "passive"))
      (node (ref "R38") (pin "2") (pinfunction "2_2") (pintype "passive"))
      (node (ref "R41") (pin "2") (pinfunction "2_2") (pintype "passive"))
      (node (ref "Remot1") (pin "1") (pinfunction "1_1") (pintype "passive"))
      (node (ref "U3") (pin "1") (pinfunction "VBAT_1") (pintype "bidirectional"))
      (node (ref "U3") (pin "24") (pinfunction "VDD_24") (pintype "power_in"))
      (node (ref "U3") (pin "36") (pinfunction "VDD_36") (pintype "power_in"))
      (node (ref "U3") (pin "48") (pinfunction "VDD_48") (pintype "power_in"))
      (node (ref "U3") (pin "9") (pinfunction "VDDA_9") (pintype "power_in"))
    )
    (net (code "3") (name "/12v") (class "Default")
      (node (ref "C10") (pin "1") (pinfunction "+_1") (pintype "passive"))
      (node (ref "C11") (pin "1") (pinfunction "+_1") (pintype "passive"))
      (node (ref "C12") (pin "2") (pinfunction "2_2") (pintype "passive"))
      (node (ref "C13") (pin "1") (pinfunction "1_1") (pintype "passive"))
      (node (ref "C9") (pin "1") (pinfunction "+_1") (pintype "passive"))
      (node (ref "D3") (pin "2") (pintype "passive"))
      (node (ref "D6") (pin "2") (pintype "passive"))
      (node (ref "K1") (pin "3") (pinfunction "T1_3") (pintype "passive"))
      (node (ref "K2") (pin "3") (pinfunction "T1_3") (pintype "passive"))
      (node (ref "P1") (pin "1") (pinfunction "1_1") (pintype "passive"))
      (node (ref "P3") (pin "1") (pinfunction "1_1") (pintype "passive"))
      (node (ref "PS1") (pin "4") (pinfunction "+VO_4") (pintype "passive"))
      (node (ref "Q3") (pin "2") (pinfunction "E_2") (pintype "passive"))
      (node (ref "R10") (pin "1") (pinfunction "1_1") (pintype "passive"))
      (node (ref "R19") (pin "1") (pinfunction "1_1") (pintype "passive"))
      (node (ref "R25") (pin "1") (pinfunction "1_1") (pintype "passive"))
      (node (ref "R3") (pin "2") (pinfunction "2_2") (pintype "passive"))
      (node (ref "U1") (pin "1") (pinfunction "VIN_1") (pintype "passive"))
    )
    (net (code "4") (name "/CLK") (class "Default")
      (node (ref "PROGRAM1") (pin "3") (pinfunction "3_3") (pintype "passive"))
      (node (ref "U3") (pin "37") (pinfunction "PA14_37") (pintype "bidirectional"))
    )
    (net (code "5") (name "/DIO") (class "Default")
      (node (ref "PROGRAM1") (pin "4") (pinfunction "4_4") (pintype "passive"))
      (node (ref "U3") (pin "34") (pinfunction "PA13_34") (pintype "bidirectional"))
    )
    (net (code "6") (name "/N") (class "Default")
      (node (ref "PS1") (pin "2") (pinfunction "AC_2_2") (pintype "passive"))
      (node (ref "T1") (pin "1") (pinfunction "1_1") (pintype "passive"))
      (node (ref "battery2") (pin "2") (pinfunction "2_2") (pintype "passive"))
      (node (ref "battery5") (pin "2") (pinfunction "2_2") (pintype "passive"))
      (node (ref "out1") (pin "2") (pinfunction "2_2") (pintype "passive"))
      (node (ref "out2") (pin "2") (pinfunction "2_2") (pintype "passive"))
    )
    (net (code "7") (name "/ON_Queqtel") (class "Default")
      (node (ref "R33") (pin "2") (pinfunction "2_2") (pintype "passive"))
      (node (ref "U3") (pin "29") (pinfunction "PA8_29") (pintype "bidirectional"))
    )
    (net (code "8") (name "/P") (class "Default")
      (node (ref "C16") (pin "2") (pinfunction "2_2") (pintype "passive"))
      (node (ref "C18") (pin "2") (pinfunction "2_2") (pintype "passive"))
      (node (ref "K1") (pin "1") (pinfunction "COM_1") (pintype "passive"))
      (node (ref "K2") (pin "1") (pinfunction "COM_1") (pintype "passive"))
      (node (ref "PS1") (pin "1") (pinfunction "AC_1_1") (pintype "passive"))
      (node (ref "T1") (pin "2") (pinfunction "2_2") (pintype "passive"))
    )
    (net (code "9") (name "/PB4") (class "Default")
      (node (ref "R28") (pin "1") (pinfunction "1_1") (pintype "passive"))
      (node (ref "U3") (pin "40") (pinfunction "PB4_40") (pintype "bidirectional"))
    )
    (net (code "10") (name "/PB12") (class "Default")
      (node (ref "R36") (pin "1") (pinfunction "1_1") (pintype "passive"))
      (node (ref "R39") (pin "1") (pinfunction "1_1") (pintype "passive"))
      (node (ref "U3") (pin "25") (pinfunction "PB12_25") (pintype "bidirectional"))
    )
    (net (code "11") (name "/PB13") (class "Default")
      (node (ref "R42") (pin "1") (pinfunction "1_1") (pintype "passive"))
      (node (ref "R43") (pin "1") (pinfunction "1_1") (pintype "passive"))
      (node (ref "U3") (pin "26") (pinfunction "PB13_26") (pintype "bidirectional"))
    )
    (net (code "12") (name "/PB14") (class "Default")
      (node (ref "R29") (pin "1") (pinfunction "1_1") (pintype "passive"))
      (node (ref "Remot1") (pin "6") (pinfunction "6_6") (pintype "passive"))
      (node (ref "U3") (pin "27") (pinfunction "PB14_27") (pintype "bidirectional"))
    )
    (net (code "13") (name "/PB15") (class "Default")
      (node (ref "R30") (pin "1") (pinfunction "1_1") (pintype "passive"))
      (node (ref "Remot1") (pin "5") (pinfunction "5_5") (pintype "passive"))
      (node (ref "U3") (pin "28") (pinfunction "PB15_28") (pintype "bidirectional"))
    )
    (net (code "14") (name "/PC13") (class "Default")
      (node (ref "R23") (pin "1") (pinfunction "1_1") (pintype "passive"))
      (node (ref "U3") (pin "2") (pinfunction "PC13-TAMPER-RTC_2") (pintype "bidirectional"))
    )
    (net (code "15") (name "/P_1") (class "Default")
      (node (ref "K1") (pin "4") (pinfunction "NO_4") (pintype "passive"))
      (node (ref "R11") (pin "2") (pintype "passive"))
      (node (ref "R6") (pin "1") (pinfunction "1_1") (pintype "passive"))
      (node (ref "R7") (pin "1") (pinfunction "1_1") (pintype "passive"))
      (node (ref "out1") (pin "1") (pinfunction "1_1") (pintype "passive"))
    )
    (net (code "16") (name "/P_2") (class "Default")
      (node (ref "K2") (pin "4") (pinfunction "NO_4") (pintype "passive"))
      (node (ref "R11") (pin "1") (pintype "passive"))
      (node (ref "R17") (pin "1") (pinfunction "1_1") (pintype "passive"))
      (node (ref "R8") (pin "1") (pinfunction "1_1") (pintype "passive"))
      (node (ref "out2") (pin "1") (pinfunction "1_1") (pintype "passive"))
    )
    (net (code "17") (name "/Pa2") (class "Default")
      (node (ref "P2") (pin "2") (pinfunction "2_2") (pintype "passive"))
      (node (ref "U3") (pin "12") (pinfunction "PA2_12") (pintype "bidirectional"))
    )
    (net (code "18") (name "/Pa3") (class "Default")
      (node (ref "P2") (pin "3") (pinfunction "3_3") (pintype "passive"))
      (node (ref "U3") (pin "13") (pinfunction "PA3_13") (pintype "bidirectional"))
    )
    (net (code "19") (name "/Pa11") (class "Default")
      (node (ref "R31") (pin "1") (pinfunction "1_1") (pintype "passive"))
      (node (ref "Remot1") (pin "4") (pinfunction "4_4") (pintype "passive"))
      (node (ref "U3") (pin "32") (pinfunction "PA11_32") (pintype "bidirectional"))
    )
    (net (code "20") (name "/Pa12") (class "Default")
      (node (ref "R32") (pin "1") (pinfunction "1_1") (pintype "passive"))
      (node (ref "Remot1") (pin "3") (pinfunction "3_3") (pintype "passive"))
      (node (ref "U3") (pin "33") (pinfunction "PA12_33") (pintype "bidirectional"))
    )
    (net (code "21") (name "/RI") (class "Default")
      (node (ref "R35") (pin "1") (pinfunction "1_1") (pintype "passive"))
      (node (ref "U2") (pin "7") (pinfunction "RI_7") (pintype "output"))
      (node (ref "U3") (pin "22") (pinfunction "PB11_22") (pintype "bidirectional"))
    )
    (net (code "22") (name "/RLY_1") (class "Default")
      (node (ref "R9") (pin "2") (pinfunction "2_2") (pintype "passive"))
      (node (ref "U3") (pin "15") (pinfunction "PA5_15") (pintype "bidirectional"))
    )
    (net (code "23") (name "/RLY_2") (class "Default")
      (node (ref "R20") (pin "2") (pinfunction "2_2") (pintype "passive"))
      (node (ref "U3") (pin "16") (pinfunction "PA6_16") (pintype "bidirectional"))
    )
    (net (code "24") (name "/RST") (class "Default")
      (node (ref "C22") (pin "2") (pinfunction "2_2") (pintype "passive"))
      (node (ref "R24") (pin "1") (pinfunction "1_1") (pintype "passive"))
      (node (ref "U3") (pin "7") (pinfunction "NRST_7") (pintype "input"))
    )
    (net (code "25") (name "/RX") (class "Default")
      (node (ref "U2") (pin "2") (pinfunction "RXD_2") (pintype "input"))
      (node (ref "U3") (pin "30") (pinfunction "PA9_30") (pintype "bidirectional"))
    )
    (net (code "26") (name "/SCL") (class "Default")
      (node (ref "IC3") (pin "6") (pinfunction "SCL_6") (pintype "passive"))
      (node (ref "R38") (pin "1") (pinfunction "1_1") (pintype "passive"))
      (node (ref "U3") (pin "42") (pinfunction "PB6_42") (pintype "bidirectional"))
    )
    (net (code "27") (name "/SDA") (class "Default")
      (node (ref "IC3") (pin "5") (pinfunction "SDA_5") (pintype "passive"))
      (node (ref "R41") (pin "1") (pinfunction "1_1") (pintype "passive"))
      (node (ref "U3") (pin "43") (pinfunction "PB7_43") (pintype "bidirectional"))
    )
    (net (code "28") (name "/SIM_CLK") (class "Default")
      (node (ref "J1") (pin "C3") (pinfunction "CLK_C3") (pintype "bidirectional"))
      (node (ref "U2") (pin "16") (pinfunction "SIM_CLK_16") (pintype "output"))
    )
    (net (code "29") (name "/SIM_IO") (class "Default")
      (node (ref "J1") (pin "C7") (pinfunction "I/O_C7") (pintype "bidirectional"))
      (node (ref "U2") (pin "15") (pinfunction "SIM_DATA_15") (pintype "bidirectional"))
    )
    (net (code "30") (name "/SIM_RST") (class "Default")
      (node (ref "J1") (pin "C2") (pinfunction "RST_C2") (pintype "input"))
      (node (ref "U2") (pin "17") (pinfunction "SIM_RST_17") (pintype "output"))
    )
    (net (code "31") (name "/TX") (class "Default")
      (node (ref "R40") (pin "2") (pinfunction "2_2") (pintype "passive"))
      (node (ref "U2") (pin "1") (pinfunction "TXD_1") (pintype "output"))
    )
    (net (code "32") (name "/V_SIM") (class "Default")
      (node (ref "C26") (pin "1") (pinfunction "+_1") (pintype "passive"))
      (node (ref "J1") (pin "C1") (pinfunction "VCC_C1") (pintype "power_in"))
      (node (ref "U2") (pin "18") (pinfunction "SIM_VDD_18") (pintype "power_in"))
    )
    (net (code "33") (name "/WC") (class "Default")
      (node (ref "IC3") (pin "7") (pinfunction "~{WC}_7") (pintype "passive"))
      (node (ref "R34") (pin "1") (pinfunction "1_1") (pintype "passive"))
      (node (ref "U3") (pin "41") (pinfunction "PB5_41") (pintype "bidirectional"))
    )
    (net (code "34") (name "/current") (class "Default")
      (node (ref "C21") (pin "2") (pinfunction "2_2") (pintype "passive"))
      (node (ref "R13") (pin "2") (pinfunction "2_2") (pintype "passive"))
      (node (ref "U3") (pin "11") (pinfunction "PA1_11") (pintype "bidirectional"))
    )
    (net (code "35") (name "/pa0") (class "Default")
      (node (ref "R3") (pin "1") (pinfunction "1_1") (pintype "passive"))
      (node (ref "R5") (pin "2") (pinfunction "2_2") (pintype "passive"))
      (node (ref "U3") (pin "10") (pinfunction "PA0_WKUP_10") (pintype "bidirectional"))
    )
    (net (code "36") (name "GND") (class "Default")
      (node (ref "2.2k") (pin "2") (pinfunction "2_2") (pintype "passive"))
      (node (ref "ANT1") (pin "2") (pinfunction "2_2") (pintype "passive"))
      (node (ref "C1") (pin "1") (pinfunction "1_1") (pintype "passive"))
      (node (ref "C10") (pin "2") (pinfunction "-_2") (pintype "passive"))
      (node (ref "C11") (pin "2") (pinfunction "-_2") (pintype "passive"))
      (node (ref "C12") (pin "1") (pinfunction "1_1") (pintype "passive"))
      (node (ref "C13") (pin "2") (pinfunction "2_2") (pintype "passive"))
      (node (ref "C14") (pin "1") (pinfunction "1_1") (pintype "passive"))
      (node (ref "C15") (pin "2") (pinfunction "2_2") (pintype "passive"))
      (node (ref "C17") (pin "2") (pinfunction "2_2") (pintype "passive"))
      (node (ref "C19") (pin "1") (pinfunction "1_1") (pintype "passive"))
      (node (ref "C2") (pin "1") (pinfunction "1_1") (pintype "passive"))
      (node (ref "C20") (pin "1") (pinfunction "1_1") (pintype "passive"))
      (node (ref "C21") (pin "1") (pinfunction "1_1") (pintype "passive"))
      (node (ref "C22") (pin "1") (pinfunction "1_1") (pintype "passive"))
      (node (ref "C23") (pin "2") (pinfunction "2_2") (pintype "passive"))
      (node (ref "C24") (pin "2") (pinfunction "-_2") (pintype "passive"))
      (node (ref "C25") (pin "2") (pinfunction "2_2") (pintype "passive"))
      (node (ref "C26") (pin "2") (pinfunction "-_2") (pintype "passive"))
      (node (ref "C27") (pin "1") (pinfunction "1_1") (pintype "passive"))
      (node (ref "C28") (pin "1") (pinfunction "1_1") (pintype "passive"))
      (node (ref "C3") (pin "1") (pinfunction "1_1") (pintype "passive"))
      (node (ref "C4") (pin "1") (pinfunction "1_1") (pintype "passive"))
      (node (ref "C5") (pin "2") (pinfunction "2_2") (pintype "passive"))
      (node (ref "C6") (pin "2") (pinfunction "2_2") (pintype "passive"))
      (node (ref "C7") (pin "2") (pinfunction "2_2") (pintype "passive"))
      (node (ref "C8") (pin "2") (pinfunction "2_2") (pintype "passive"))
      (node (ref "C9") (pin "2") (pinfunction "-_2") (pintype "passive"))
      (node (ref "D1") (pin "1") (pintype "passive"))
      (node (ref "D4") (pin "1") (pintype "passive"))
      (node (ref "D8") (pin "1") (pintype "passive"))
      (node (ref "IC1") (pin "1") (pinfunction "ADJ/GND_1") (pintype "passive"))
      (node (ref "IC2") (pin "1") (pinfunction "TEMP_1") (pintype "passive"))
      (node (ref "IC2") (pin "3") (pinfunction "GND_3") (pintype "passive"))
      (node (ref "IC2") (pin "9") (pinfunction "EAD_9") (pintype "passive"))
      (node (ref "IC3") (pin "1") (pinfunction "E0_1") (pintype "passive"))
      (node (ref "IC3") (pin "2") (pinfunction "E1_2") (pintype "passive"))
      (node (ref "IC3") (pin "3") (pinfunction "E2_3") (pintype "passive"))
      (node (ref "IC3") (pin "4") (pinfunction "VSS_4") (pintype "passive"))
      (node (ref "J1") (pin "C5") (pinfunction "GND_C5") (pintype "power_in"))
      (node (ref "LD1") (pin "2") (pinfunction "K_2") (pintype "passive"))
      (node (ref "LD2") (pin "2") (pinfunction "K_2") (pintype "passive"))
      (node (ref "LED5") (pin "1") (pinfunction "K_1") (pintype "passive"))
      (node (ref "Out3") (pin "1") (pinfunction "1_1") (pintype "passive"))
      (node (ref "P1") (pin "3") (pinfunction "3_3") (pintype "passive"))
      (node (ref "P2") (pin "1") (pinfunction "1_1") (pintype "passive"))
      (node (ref "P3") (pin "3") (pinfunction "3_3") (pintype "passive"))
      (node (ref "PROGRAM1") (pin "1") (pinfunction "1_1") (pintype "passive"))
      (node (ref "PS1") (pin "3") (pinfunction "-VO_3") (pintype "passive"))
      (node (ref "Q1") (pin "2") (pinfunction "E_2") (pintype "passive"))
      (node (ref "Q2") (pin "2") (pinfunction "E_2") (pintype "passive"))
      (node (ref "Q4") (pin "3") (pinfunction "S_3") (pintype "passive"))
      (node (ref "Q5") (pin "2") (pinfunction "E_2") (pintype "passive"))
      (node (ref "Q6") (pin "2") (pinfunction "E_2") (pintype "passive"))
      (node (ref "R14") (pin "2") (pinfunction "2_2") (pintype "passive"))
      (node (ref "R16") (pin "1") (pinfunction "1_1") (pintype "passive"))
      (node (ref "R22") (pin "2") (pinfunction "2_2") (pintype "passive"))
      (node (ref "R27") (pin "2") (pinfunction "2_2") (pintype "passive"))
      (node (ref "R29") (pin "2") (pinfunction "2_2") (pintype "passive"))
      (node (ref "R30") (pin "2") (pinfunction "2_2") (pintype "passive"))
      (node (ref "R31") (pin "2") (pinfunction "2_2") (pintype "passive"))
      (node (ref "R32") (pin "2") (pinfunction "2_2") (pintype "passive"))
      (node (ref "R4") (pin "1") (pinfunction "1_1") (pintype "passive"))
      (node (ref "R43") (pin "2") (pinfunction "2_2") (pintype "passive"))
      (node (ref "R5") (pin "1") (pinfunction "1_1") (pintype "passive"))
      (node (ref "Remot1") (pin "2") (pinfunction "2_2") (pintype "passive"))
      (node (ref "U1") (pin "3") (pinfunction "GND_3") (pintype "passive"))
      (node (ref "U1") (pin "5") (pinfunction "ON/OFF_5") (pintype "passive"))
      (node (ref "U2") (pin "13") (pinfunction "GND_13") (pintype "power_in"))
      (node (ref "U2") (pin "19") (pinfunction "GND_19") (pintype "power_in"))
      (node (ref "U2") (pin "21") (pinfunction "GND_21") (pintype "power_in"))
      (node (ref "U2") (pin "27") (pinfunction "GND_27") (pintype "power_in"))
      (node (ref "U2") (pin "30") (pinfunction "GND_30") (pintype "power_in"))
      (node (ref "U2") (pin "31") (pinfunction "GND_31") (pintype "power_in"))
      (node (ref "U2") (pin "33") (pinfunction "GND_33") (pintype "power_in"))
      (node (ref "U2") (pin "36") (pinfunction "GND_36") (pintype "power_in"))
      (node (ref "U2") (pin "37") (pinfunction "GND_37") (pintype "power_in"))
      (node (ref "U2") (pin "8") (pinfunction "GND_8") (pintype "power_in"))
      (node (ref "U3") (pin "23") (pinfunction "VSS_23") (pintype "power_in"))
      (node (ref "U3") (pin "35") (pinfunction "VSS_35") (pintype "power_in"))
      (node (ref "U3") (pin "44") (pinfunction "BOOT0_44") (pintype "input"))
      (node (ref "U3") (pin "47") (pinfunction "VSS_47") (pintype "power_in"))
      (node (ref "U3") (pin "8") (pinfunction "VSSA_8") (pintype "power_in"))
      (node (ref "battery1") (pin "1") (pinfunction "1_1") (pintype "passive"))
      (node (ref "battery3") (pin "2") (pinfunction "2_2") (pintype "passive"))
      (node (ref "battery4") (pin "1") (pinfunction "1_1") (pintype "passive"))
      (node (ref "cs1") (pin "1") (pinfunction "+_1") (pintype "passive"))
    )
    (net (code "37") (name "Net-(Buzzer1-Pad1)") (class "Default")
      (node (ref "Buzzer1") (pin "1") (pinfunction "1_1") (pintype "passive"))
      (node (ref "Out3") (pin "2") (pinfunction "2_2") (pintype "passive"))
      (node (ref "R25") (pin "2") (pinfunction "2_2") (pintype "passive"))
    )
    (net (code "38") (name "Net-(C16-Pad1)") (class "Default")
      (node (ref "C16") (pin "1") (pinfunction "1_1") (pintype "passive"))
      (node (ref "R6") (pin "2") (pinfunction "2_2") (pintype "passive"))
    )
    (net (code "39") (name "Net-(C18-Pad1)") (class "Default")
      (node (ref "C18") (pin "1") (pinfunction "1_1") (pintype "passive"))
      (node (ref "R17") (pin "2") (pinfunction "2_2") (pintype "passive"))
    )
    (net (code "40") (name "Net-(C19-Pad2)") (class "Default")
      (node (ref "C19") (pin "2") (pinfunction "2_2") (pintype "passive"))
      (node (ref "D5") (pin "2") (pintype "passive"))
      (node (ref "D7") (pin "2") (pintype "passive"))
      (node (ref "R12") (pin "1") (pinfunction "1_1") (pintype "passive"))
      (node (ref "R16") (pin "2") (pinfunction "2_2") (pintype "passive"))
    )
    (net (code "41") (name "Net-(C20-Pad2)") (class "Default")
      (node (ref "C20") (pin "2") (pinfunction "2_2") (pintype "passive"))
      (node (ref "R12") (pin "2") (pinfunction "2_2") (pintype "passive"))
      (node (ref "R13") (pin "1") (pinfunction "1_1") (pintype "passive"))
    )
    (net (code "42") (name "Net-(D4-Pad2)") (class "Default")
      (node (ref "D4") (pin "2") (pintype "passive"))
      (node (ref "D7") (pin "1") (pintype "passive"))
      (node (ref "T2") (pin "1") (pinfunction "1_1") (pintype "passive"))
    )
    (net (code "43") (name "Net-(D5-Pad1)") (class "Default")
      (node (ref "D5") (pin "1") (pintype "passive"))
      (node (ref "D8") (pin "2") (pintype "passive"))
      (node (ref "T2") (pin "2") (pinfunction "2_2") (pintype "passive"))
    )
    (net (code "44") (name "Net-(D_BATT1-PadA)") (class "Default")
      (node (ref "D_BATT1") (pin "A") (pinfunction "A_A") (pintype "passive"))
      (node (ref "PROGRAM1") (pin "2") (pinfunction "2_2") (pintype "passive"))
    )
    (net (code "45") (name "Net-(IC2-BAT)") (class "Default")
      (node (ref "D2") (pin "A") (pinfunction "A_A") (pintype "passive"))
      (node (ref "IC2") (pin "5") (pinfunction "BAT_5") (pintype "passive"))
      (node (ref "S1") (pin "1") (pinfunction "1_1") (pintype "passive"))
    )
    (net (code "46") (name "Net-(IC2-PROG)") (class "Default")
      (node (ref "2.2k") (pin "1") (pinfunction "1_1") (pintype "passive"))
      (node (ref "IC2") (pin "2") (pinfunction "PROG_2") (pintype "passive"))
    )
    (net (code "47") (name "Net-(IC2-~{CHRG})") (class "Default")
      (node (ref "IC2") (pin "7") (pinfunction "~{CHRG}_7") (pintype "passive"))
      (node (ref "R15") (pin "2") (pinfunction "2_2") (pintype "passive"))
    )
    (net (code "48") (name "Net-(IC2-~{STDBY})") (class "Default")
      (node (ref "IC2") (pin "6") (pinfunction "~{STDBY}_6") (pintype "passive"))
      (node (ref "R21") (pin "2") (pinfunction "2_2") (pintype "passive"))
    )
    (net (code "49") (name "Net-(K1-T2)") (class "Default")
      (node (ref "D3") (pin "1") (pintype "passive"))
      (node (ref "K1") (pin "2") (pinfunction "T2_2") (pintype "passive"))
      (node (ref "LED1") (pin "1") (pinfunction "K_1") (pintype "passive"))
      (node (ref "Q1") (pin "3") (pinfunction "C_3") (pintype "passive"))
      (node (ref "battery1") (pin "2") (pinfunction "2_2") (pintype "passive"))
    )
    (net (code "50") (name "Net-(K2-T2)") (class "Default")
      (node (ref "D6") (pin "1") (pintype "passive"))
      (node (ref "K2") (pin "2") (pinfunction "T2_2") (pintype "passive"))
      (node (ref "LED3") (pin "1") (pinfunction "K_1") (pintype "passive"))
      (node (ref "Q2") (pin "3") (pinfunction "C_3") (pintype "passive"))
      (node (ref "battery4") (pin "2") (pinfunction "2_2") (pintype "passive"))
    )
    (net (code "51") (name "Net-(LD1-A)") (class "Default")
      (node (ref "LD1") (pin "1") (pinfunction "A_1") (pintype "passive"))
      (node (ref "R2") (pin "2") (pinfunction "2_2") (pintype "passive"))
    )
    (net (code "52") (name "Net-(LD2-A)") (class "Default")
      (node (ref "LD2") (pin "1") (pinfunction "A_1") (pintype "passive"))
      (node (ref "R23") (pin "2") (pinfunction "2_2") (pintype "passive"))
    )
    (net (code "53") (name "Net-(LED1-A)") (class "Default")
      (node (ref "LED1") (pin "2") (pinfunction "A_2") (pintype "passive"))
      (node (ref "R10") (pin "2") (pinfunction "2_2") (pintype "passive"))
    )
    (net (code "54") (name "Net-(LED2-K)") (class "Default")
      (node (ref "LED2") (pin "1") (pinfunction "K_1") (pintype "passive"))
      (node (ref "R15") (pin "1") (pinfunction "1_1") (pintype "passive"))
    )
    (net (code "55") (name "Net-(LED3-A)") (class "Default")
      (node (ref "LED3") (pin "2") (pinfunction "A_2") (pintype "passive"))
      (node (ref "R19") (pin "2") (pinfunction "2_2") (pintype "passive"))
    )
    (net (code "56") (name "Net-(LED4-K)") (class "Default")
      (node (ref "LED4") (pin "1") (pinfunction "K_1") (pintype "passive"))
      (node (ref "R21") (pin "1") (pinfunction "1_1") (pintype "passive"))
    )
    (net (code "57") (name "Net-(LED5-A)") (class "Default")
      (node (ref "4.7k") (pin "2") (pinfunction "2_2") (pintype "passive"))
      (node (ref "LED5") (pin "2") (pinfunction "A_2") (pintype "passive"))
    )
    (net (code "58") (name "Net-(P1-Pad2)") (class "Default")
      (node (ref "P1") (pin "2") (pinfunction "2_2") (pintype "passive"))
      (node (ref "R39") (pin "2") (pinfunction "2_2") (pintype "passive"))
    )
    (net (code "59") (name "Net-(P3-Pad2)") (class "Default")
      (node (ref "P3") (pin "2") (pinfunction "2_2") (pintype "passive"))
      (node (ref "R42") (pin "2") (pinfunction "2_2") (pintype "passive"))
    )
    (net (code "60") (name "Net-(Q1-B)") (class "Default")
      (node (ref "Q1") (pin "1") (pinfunction "B_1") (pintype "passive"))
      (node (ref "R14") (pin "1") (pinfunction "1_1") (pintype "passive"))
      (node (ref "R9") (pin "1") (pinfunction "1_1") (pintype "passive"))
    )
    (net (code "61") (name "Net-(Q2-B)") (class "Default")
      (node (ref "Q2") (pin "1") (pinfunction "B_1") (pintype "passive"))
      (node (ref "R20") (pin "1") (pinfunction "1_1") (pintype "passive"))
      (node (ref "R22") (pin "1") (pinfunction "1_1") (pintype "passive"))
    )
    (net (code "62") (name "Net-(Q3-B)") (class "Default")
      (node (ref "Q3") (pin "1") (pinfunction "B_1") (pintype "passive"))
      (node (ref "R26") (pin "2") (pinfunction "2_2") (pintype "passive"))
    )
    (net (code "63") (name "Net-(Q3-C)") (class "Default")
      (node (ref "Q3") (pin "3") (pinfunction "C_3") (pintype "passive"))
      (node (ref "Q4") (pin "1") (pinfunction "G_1") (pintype "passive"))
      (node (ref "R27") (pin "1") (pinfunction "1_1") (pintype "passive"))
    )
    (net (code "64") (name "Net-(Q4-D)") (class "Default")
      (node (ref "Buzzer1") (pin "2") (pinfunction "2_2") (pintype "passive"))
      (node (ref "Q4") (pin "2") (pinfunction "D_2") (pintype "passive"))
    )
    (net (code "65") (name "Net-(Q5-B)") (class "Default")
      (node (ref "Q5") (pin "1") (pinfunction "B_1") (pintype "passive"))
      (node (ref "R28") (pin "2") (pinfunction "2_2") (pintype "passive"))
    )
    (net (code "66") (name "Net-(Q5-C)") (class "Default")
      (node (ref "Q5") (pin "3") (pinfunction "C_3") (pintype "passive"))
      (node (ref "R26") (pin "1") (pinfunction "1_1") (pintype "passive"))
    )
    (net (code "67") (name "Net-(Q6-B)") (class "Default")
      (node (ref "Q6") (pin "1") (pinfunction "B_1") (pintype "passive"))
      (node (ref "R33") (pin "1") (pinfunction "1_1") (pintype "passive"))
    )
    (net (code "68") (name "Net-(Q6-C)") (class "Default")
      (node (ref "Q6") (pin "3") (pinfunction "C_3") (pintype "passive"))
      (node (ref "U2") (pin "39") (pinfunction "PWRKEY_39") (pintype "input"))
    )
    (net (code "69") (name "Net-(R7-Pad2)") (class "Default")
      (node (ref "R7") (pin "2") (pinfunction "2_2") (pintype "passive"))
      (node (ref "battery2") (pin "1") (pinfunction "1_1") (pintype "passive"))
    )
    (net (code "70") (name "Net-(R8-Pad2)") (class "Default")
      (node (ref "R8") (pin "2") (pinfunction "2_2") (pintype "passive"))
      (node (ref "battery5") (pin "1") (pinfunction "1_1") (pintype "passive"))
    )
    (net (code "71") (name "Net-(S1-Pad2)") (class "Default")
      (node (ref "S1") (pin "2") (pinfunction "2_2") (pintype "passive"))
      (node (ref "battery3") (pin "1") (pinfunction "1_1") (pintype "passive"))
    )
    (net (code "72") (name "Net-(U1-FB)") (class "Default")
      (node (ref "R1") (pin "1") (pinfunction "1_1") (pintype "passive"))
      (node (ref "R4") (pin "2") (pinfunction "2_2") (pintype "passive"))
      (node (ref "U1") (pin "4") (pinfunction "FB_4") (pintype "passive"))
    )
    (net (code "73") (name "Net-(U1-OUT)") (class "Default")
      (node (ref "D1") (pin "2") (pintype "passive"))
      (node (ref "L1") (pin "1") (pinfunction "1_1") (pintype "passive"))
      (node (ref "U1") (pin "2") (pinfunction "OUT_2") (pintype "passive"))
    )
    (net (code "74") (name "Net-(U2-NETLIGHT)") (class "Default")
      (node (ref "4.7k") (pin "1") (pinfunction "1_1") (pintype "passive"))
      (node (ref "U2") (pin "41") (pinfunction "NETLIGHT_41") (pintype "output"))
    )
    (net (code "75") (name "Net-(U2-RF_ANT)") (class "Default")
      (node (ref "ANT1") (pin "1") (pinfunction "1_1") (pintype "passive"))
      (node (ref "U2") (pin "32") (pinfunction "RF_ANT_32") (pintype "bidirectional"))
    )
    (net (code "76") (name "Net-(U3-PA10)") (class "Default")
      (node (ref "R40") (pin "1") (pinfunction "1_1") (pintype "passive"))
      (node (ref "U3") (pin "31") (pinfunction "PA10_31") (pintype "bidirectional"))
    )
    (net (code "77") (name "Net-(U3-PD0_OSC_IN)") (class "Default")
      (node (ref "C27") (pin "2") (pinfunction "2_2") (pintype "passive"))
      (node (ref "U3") (pin "5") (pinfunction "PD0_OSC_IN_5") (pintype "bidirectional"))
      (node (ref "Y1") (pin "1") (pinfunction "1_1") (pintype "passive"))
    )
    (net (code "78") (name "Net-(U3-PD1_OSC_OUT)") (class "Default")
      (node (ref "C28") (pin "2") (pinfunction "2_2") (pintype "passive"))
      (node (ref "U3") (pin "6") (pinfunction "PD1_OSC_OUT_6") (pintype "bidirectional"))
      (node (ref "Y1") (pin "2") (pinfunction "2_2") (pintype "passive"))
    )
    (net (code "79") (name "unconnected-(J1-VPP-PadC6)") (class "Default")
      (node (ref "J1") (pin "C6") (pinfunction "VPP_C6") (pintype "power_in"))
    )
    (net (code "80") (name "unconnected-(J2-Pad1)") (class "Default")
      (node (ref "J2") (pin "1") (pinfunction "1_1") (pintype "passive"))
    )
    (net (code "81") (name "unconnected-(J3-Pad1)") (class "Default")
      (node (ref "J3") (pin "1") (pinfunction "1_1") (pintype "passive"))
    )
    (net (code "82") (name "unconnected-(J4-Pad1)") (class "Default")
      (node (ref "J4") (pin "1") (pinfunction "1_1") (pintype "passive"))
    )
    (net (code "83") (name "unconnected-(J5-Pad1)") (class "Default")
      (node (ref "J5") (pin "1") (pinfunction "1_1") (pintype "passive"))
    )
    (net (code "84") (name "unconnected-(J6-Pad1)") (class "Default")
      (node (ref "J6") (pin "1") (pinfunction "1_1") (pintype "passive"))
    )
    (net (code "85") (name "unconnected-(J7-Pad1)") (class "Default")
      (node (ref "J7") (pin "1") (pinfunction "1_1") (pintype "passive"))
    )
    (net (code "86") (name "unconnected-(K1-NC-Pad5)") (class "Default")
      (node (ref "K1") (pin "5") (pinfunction "NC_5") (pintype "passive"))
    )
    (net (code "87") (name "unconnected-(K2-NC-Pad5)") (class "Default")
      (node (ref "K2") (pin "5") (pinfunction "NC_5") (pintype "passive"))
    )
    (net (code "88") (name "unconnected-(Remot1-Pad7)") (class "Default")
      (node (ref "Remot1") (pin "7") (pinfunction "7_7") (pintype "passive"))
    )
    (net (code "89") (name "unconnected-(S1-Pad3)") (class "Default")
      (node (ref "S1") (pin "3") (pinfunction "3_3") (pintype "passive"))
    )
    (net (code "90") (name "unconnected-(U2-ADC-Pad38)") (class "Default")
      (node (ref "U2") (pin "38") (pinfunction "ADC_38") (pintype "input+no_connect"))
    )
    (net (code "91") (name "unconnected-(U2-CTS-Pad4)") (class "Default")
      (node (ref "U2") (pin "4") (pinfunction "CTS_4") (pintype "output"))
    )
    (net (code "92") (name "unconnected-(U2-DBG_RXD-Pad26)") (class "Default")
      (node (ref "U2") (pin "26") (pinfunction "DBG_RXD_26") (pintype "input+no_connect"))
    )
    (net (code "93") (name "unconnected-(U2-DBG_TXD-Pad25)") (class "Default")
      (node (ref "U2") (pin "25") (pinfunction "DBG_TXD_25") (pintype "output"))
    )
    (net (code "94") (name "unconnected-(U2-DCD-Pad5)") (class "Default")
      (node (ref "U2") (pin "5") (pinfunction "DCD_5") (pintype "output"))
    )
    (net (code "95") (name "unconnected-(U2-DTR-Pad6)") (class "Default")
      (node (ref "U2") (pin "6") (pinfunction "DTR_6") (pintype "input+no_connect"))
    )
    (net (code "96") (name "unconnected-(U2-MICN-Pad10)") (class "Default")
      (node (ref "U2") (pin "10") (pinfunction "MICN_10") (pintype "input+no_connect"))
    )
    (net (code "97") (name "unconnected-(U2-MICP-Pad9)") (class "Default")
      (node (ref "U2") (pin "9") (pinfunction "MICP_9") (pintype "input+no_connect"))
    )
    (net (code "98") (name "unconnected-(U2-NC-Pad20)") (class "Default")
      (node (ref "U2") (pin "20") (pinfunction "NC_20") (pintype "passive"))
    )
    (net (code "99") (name "unconnected-(U2-RESERVED-Pad24)") (class "Default")
      (node (ref "U2") (pin "24") (pinfunction "RESERVED_24") (pintype "passive"))
    )
    (net (code "100") (name "unconnected-(U2-RFTXMON-Pad29)") (class "Default")
      (node (ref "U2") (pin "29") (pinfunction "RFTXMON_29") (pintype "output"))
    )
    (net (code "101") (name "unconnected-(U2-RTS-Pad3)") (class "Default")
      (node (ref "U2") (pin "3") (pinfunction "RTS_3") (pintype "input+no_connect"))
    )
    (net (code "102") (name "unconnected-(U2-RXD_AUX-Pad23)") (class "Default")
      (node (ref "U2") (pin "23") (pinfunction "RXD_AUX_23") (pintype "input+no_connect"))
    )
    (net (code "103") (name "unconnected-(U2-SIM_PRESENCE-Pad14)") (class "Default")
      (node (ref "U2") (pin "14") (pinfunction "SIM_PRESENCE_14") (pintype "input+no_connect"))
    )
    (net (code "104") (name "unconnected-(U2-SPKN-Pad12)") (class "Default")
      (node (ref "U2") (pin "12") (pinfunction "SPKN_12") (pintype "output"))
    )
    (net (code "105") (name "unconnected-(U2-SPKP-Pad11)") (class "Default")
      (node (ref "U2") (pin "11") (pinfunction "SPKP_11") (pintype "output"))
    )
    (net (code "106") (name "unconnected-(U2-STATUS-Pad42)") (class "Default")
      (node (ref "U2") (pin "42") (pinfunction "STATUS_42") (pintype "output"))
    )
    (net (code "107") (name "unconnected-(U2-TXD_AUX-Pad22)") (class "Default")
      (node (ref "U2") (pin "22") (pinfunction "TXD_AUX_22") (pintype "output"))
    )
    (net (code "108") (name "unconnected-(U2-VDD_EXT-Pad40)") (class "Default")
      (node (ref "U2") (pin "40") (pinfunction "VDD_EXT_40") (pintype "power_in"))
    )
    (net (code "109") (name "unconnected-(U2-VRTC-Pad28)") (class "Default")
      (node (ref "U2") (pin "28") (pinfunction "VRTC_28") (pintype "power_in"))
    )
    (net (code "110") (name "unconnected-(U3-PA4-Pad14)") (class "Default")
      (node (ref "U3") (pin "14") (pinfunction "PA4_14") (pintype "bidirectional"))
    )
    (net (code "111") (name "unconnected-(U3-PA7-Pad17)") (class "Default")
      (node (ref "U3") (pin "17") (pinfunction "PA7_17") (pintype "bidirectional"))
    )
    (net (code "112") (name "unconnected-(U3-PA15-Pad38)") (class "Default")
      (node (ref "U3") (pin "38") (pinfunction "PA15_38") (pintype "bidirectional"))
    )
    (net (code "113") (name "unconnected-(U3-PB0-Pad18)") (class "Default")
      (node (ref "U3") (pin "18") (pinfunction "PB0_18") (pintype "bidirectional"))
    )
    (net (code "114") (name "unconnected-(U3-PB1-Pad19)") (class "Default")
      (node (ref "U3") (pin "19") (pinfunction "PB1_19") (pintype "bidirectional"))
    )
    (net (code "115") (name "unconnected-(U3-PB2-Pad20)") (class "Default")
      (node (ref "U3") (pin "20") (pinfunction "PB2_20") (pintype "bidirectional"))
    )
    (net (code "116") (name "unconnected-(U3-PB3-Pad39)") (class "Default")
      (node (ref "U3") (pin "39") (pinfunction "PB3_39") (pintype "bidirectional"))
    )
    (net (code "117") (name "unconnected-(U3-PB8-Pad45)") (class "Default")
      (node (ref "U3") (pin "45") (pinfunction "PB8_45") (pintype "bidirectional"))
    )
    (net (code "118") (name "unconnected-(U3-PB9-Pad46)") (class "Default")
      (node (ref "U3") (pin "46") (pinfunction "PB9_46") (pintype "bidirectional"))
    )
    (net (code "119") (name "unconnected-(U3-PB10-Pad21)") (class "Default")
      (node (ref "U3") (pin "21") (pinfunction "PB10_21") (pintype "bidirectional"))
    )
    (net (code "120") (name "unconnected-(U3-PC14-OSC32_IN-Pad3)") (class "Default")
      (node (ref "U3") (pin "3") (pinfunction "PC14-OSC32_IN_3") (pintype "bidirectional"))
    )
    (net (code "121") (name "unconnected-(U3-PC15-OSC32_OUT-Pad4)") (class "Default")
      (node (ref "U3") (pin "4") (pinfunction "PC15-OSC32_OUT_4") (pintype "bidirectional"))
    )
  )
)
